# board1.net
KiCad netlist of a schematic drawn in Altium Designer
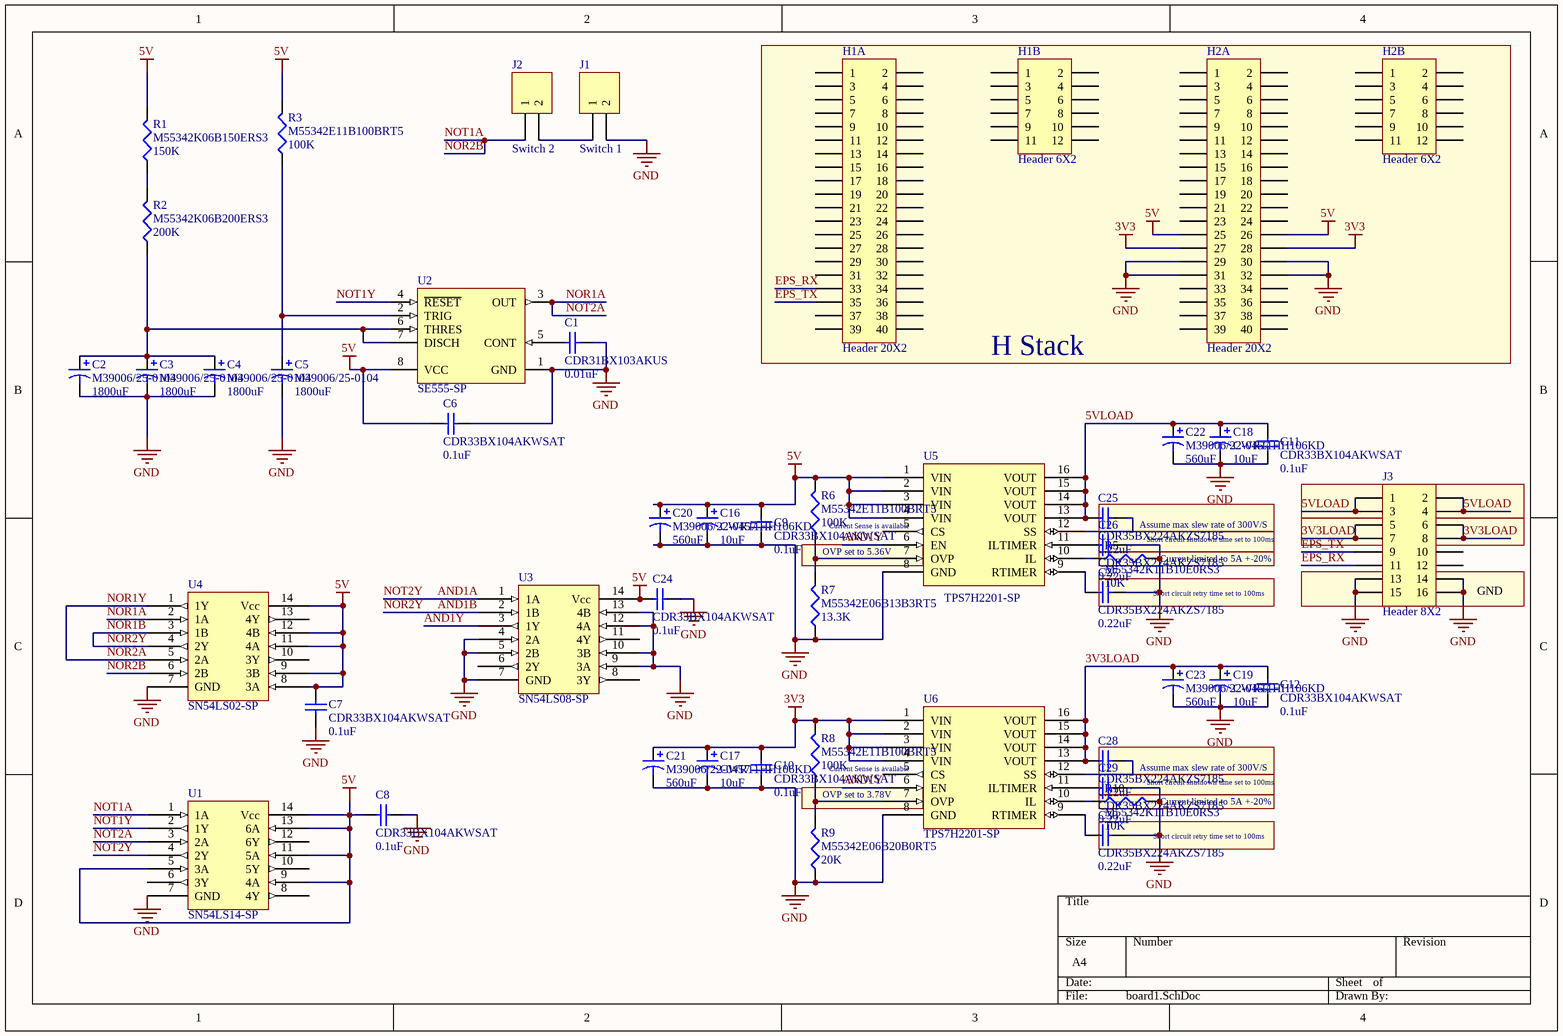
[diagram p0: board1.SchDoc]

(export (version "E")
  (design (tool "Eeschema 10.0.6"))
  (components
    (comp (ref "C1")
      (value "CDR31BX103AKUS")
      (footprint "*RESC2012X64N")
      (description "0.01uF")
      (fields (field (name "ALTIUM_VALUE") "0.01uF"))
      (libsource (lib "Capacitors") (part "CDR31BX103AKUS"))
    )
    (comp (ref "C2")
      (value "M39006/25-0104")
      (footprint "M39006/25-0104")
      (description "1800uF")
      (fields (field (name "ALTIUM_VALUE") "1800uF"))
      (libsource (lib "Capacitors") (part "M39006/25-0104"))
    )
    (comp (ref "C3")
      (value "M39006/25-0104")
      (footprint "M39006/25-0104")
      (description "1800uF")
      (fields (field (name "ALTIUM_VALUE") "1800uF"))
      (libsource (lib "Capacitors") (part "M39006/25-0104"))
    )
    (comp (ref "C4")
      (value "M39006/25-0104")
      (footprint "M39006/25-0104")
      (description "1800uF")
      (fields (field (name "ALTIUM_VALUE") "1800uF"))
      (libsource (lib "Capacitors") (part "M39006/25-0104"))
    )
    (comp (ref "C5")
      (value "M39006/25-0104")
      (footprint "M39006/25-0104")
      (description "1800uF")
      (fields (field (name "ALTIUM_VALUE") "1800uF"))
      (libsource (lib "Capacitors") (part "M39006/25-0104"))
    )
    (comp (ref "C6")
      (value "CDR33BX104AKWSAT")
      (footprint "*CAPC3225X125N")
      (description "0.1uF")
      (fields (field (name "ALTIUM_VALUE") "0.1uF"))
      (libsource (lib "Capacitors") (part "CDR33BX104AKWSAT"))
    )
    (comp (ref "C7")
      (value "CDR33BX104AKWSAT")
      (footprint "*CAPC3225X125N")
      (description "0.1uF")
      (fields (field (name "ALTIUM_VALUE") "0.1uF"))
      (libsource (lib "Capacitors") (part "CDR33BX104AKWSAT"))
    )
    (comp (ref "C8")
      (value "CDR33BX104AKWSAT")
      (footprint "*CAPC3225X125N")
      (description "0.1uF")
      (fields (field (name "ALTIUM_VALUE") "0.1uF"))
      (libsource (lib "Capacitors") (part "CDR33BX104AKWSAT"))
    )
    (comp (ref "C9")
      (value "CDR33BX104AKWSAT")
      (footprint "*CAPC3225X125N")
      (description "0.1uF")
      (fields (field (name "ALTIUM_VALUE") "0.1uF"))
      (libsource (lib "Capacitors") (part "CDR33BX104AKWSAT"))
    )
    (comp (ref "C10")
      (value "CDR33BX104AKWSAT")
      (footprint "*CAPC3225X125N")
      (description "0.1uF")
      (fields (field (name "ALTIUM_VALUE") "0.1uF"))
      (libsource (lib "Capacitors") (part "CDR33BX104AKWSAT"))
    )
    (comp (ref "C11")
      (value "CDR33BX104AKWSAT")
      (footprint "*CAPC3225X125N")
      (description "0.1uF")
      (fields (field (name "ALTIUM_VALUE") "0.1uF"))
      (libsource (lib "Capacitors") (part "CDR33BX104AKWSAT"))
    )
    (comp (ref "C12")
      (value "CDR33BX104AKWSAT")
      (footprint "*CAPC3225X125N")
      (description "0.1uF")
      (fields (field (name "ALTIUM_VALUE") "0.1uF"))
      (libsource (lib "Capacitors") (part "CDR33BX104AKWSAT"))
    )
    (comp (ref "C16")
      (value "CWR11HH106KD")
      (footprint "*CAPCP6032X280N")
      (description "10uF")
      (fields (field (name "ALTIUM_VALUE") "10uF"))
      (libsource (lib "Capacitors") (part "CWR11HH106KD"))
    )
    (comp (ref "C17")
      (value "CWR11HH106KD")
      (footprint "*CAPCP6032X280N")
      (description "10uF")
      (fields (field (name "ALTIUM_VALUE") "10uF"))
      (libsource (lib "Capacitors") (part "CWR11HH106KD"))
    )
    (comp (ref "C18")
      (value "CWR11HH106KD")
      (footprint "*CAPCP6032X280N")
      (description "10uF")
      (fields (field (name "ALTIUM_VALUE") "10uF"))
      (libsource (lib "Capacitors") (part "CWR11HH106KD"))
    )
    (comp (ref "C19")
      (value "CWR11HH106KD")
      (footprint "*CAPCP6032X280N")
      (description "10uF")
      (fields (field (name "ALTIUM_VALUE") "10uF"))
      (libsource (lib "Capacitors") (part "CWR11HH106KD"))
    )
    (comp (ref "C20")
      (value "M39006/22-0457")
      (footprint "M39006/22-0457")
      (description "560uF")
      (fields (field (name "ALTIUM_VALUE") "560uF"))
      (libsource (lib "Capacitors") (part "M39006/22-0457"))
    )
    (comp (ref "C21")
      (value "M39006/22-0457")
      (footprint "M39006/22-0457")
      (description "560uF")
      (fields (field (name "ALTIUM_VALUE") "560uF"))
      (libsource (lib "Capacitors") (part "M39006/22-0457"))
    )
    (comp (ref "C22")
      (value "M39006/22-0457")
      (footprint "M39006/22-0457")
      (description "560uF")
      (fields (field (name "ALTIUM_VALUE") "560uF"))
      (libsource (lib "Capacitors") (part "M39006/22-0457"))
    )
    (comp (ref "C23")
      (value "M39006/22-0457")
      (footprint "M39006/22-0457")
      (description "560uF")
      (fields (field (name "ALTIUM_VALUE") "560uF"))
      (libsource (lib "Capacitors") (part "M39006/22-0457"))
    )
    (comp (ref "C24")
      (value "CDR33BX104AKWSAT")
      (footprint "*CAPC3225X125N")
      (description "0.1uF")
      (fields (field (name "ALTIUM_VALUE") "0.1uF"))
      (libsource (lib "Capacitors") (part "CDR33BX104AKWSAT"))
    )
    (comp (ref "C25")
      (value "CDR35BX224AKZS7185")
      (footprint "*CAPC4663X340N")
      (description "0.22uF")
      (fields (field (name "ALTIUM_VALUE") "0.22uF"))
      (libsource (lib "Capacitors") (part "CDR35BX224AKZS7185"))
    )
    (comp (ref "C26")
      (value "CDR35BX224AKZS7185")
      (footprint "*CAPC4663X340N")
      (description "0.22uF")
      (fields (field (name "ALTIUM_VALUE") "0.22uF"))
      (libsource (lib "Capacitors") (part "CDR35BX224AKZS7185"))
    )
    (comp (ref "C27")
      (value "CDR35BX224AKZS7185")
      (footprint "*CAPC4663X340N")
      (description "0.22uF")
      (fields (field (name "ALTIUM_VALUE") "0.22uF"))
      (libsource (lib "Capacitors") (part "CDR35BX224AKZS7185"))
    )
    (comp (ref "C28")
      (value "CDR35BX224AKZS7185")
      (footprint "*CAPC4663X340N")
      (description "0.22uF")
      (fields (field (name "ALTIUM_VALUE") "0.22uF"))
      (libsource (lib "Capacitors") (part "CDR35BX224AKZS7185"))
    )
    (comp (ref "C29")
      (value "CDR35BX224AKZS7185")
      (footprint "*CAPC4663X340N")
      (description "0.22uF")
      (fields (field (name "ALTIUM_VALUE") "0.22uF"))
      (libsource (lib "Capacitors") (part "CDR35BX224AKZS7185"))
    )
    (comp (ref "C30")
      (value "CDR35BX224AKZS7185")
      (footprint "*CAPC4663X340N")
      (description "0.22uF")
      (fields (field (name "ALTIUM_VALUE") "0.22uF"))
      (libsource (lib "Capacitors") (part "CDR35BX224AKZS7185"))
    )
    (comp (ref "H1A")
      (value "Header 20X2")
      (footprint "HDR2X20")
      (description "Header, 20-Pin, Dual row")
      (fields (field (name "PUBLISHER") "Altium Limited"))
      (libsource (lib "Miscellaneous Connectors") (part "Header 20X2"))
    )
    (comp (ref "H1B")
      (value "Header 6X2")
      (footprint "HDR2X6")
      (description "Header, 6-Pin, Dual row")
      (fields (field (name "PUBLISHER") "Altium Limited"))
      (libsource (lib "Miscellaneous Connectors") (part "Header 6X2"))
    )
    (comp (ref "H2A")
      (value "Header 20X2")
      (footprint "HDR2X20")
      (description "Header, 20-Pin, Dual row")
      (fields (field (name "PUBLISHER") "Altium Limited"))
      (libsource (lib "Miscellaneous Connectors") (part "Header 20X2"))
    )
    (comp (ref "H2B")
      (value "Header 6X2")
      (footprint "HDR2X6")
      (description "Header, 6-Pin, Dual row")
      (fields (field (name "PUBLISHER") "Altium Limited"))
      (libsource (lib "Miscellaneous Connectors") (part "Header 6X2"))
    )
    (comp (ref "J1")
      (value "Switch 1")
      (footprint "HDR1X2")
      (description "Header, 2-Pin")
      (fields (field (name "PUBLISHER") "Altium Limited"))
      (libsource (lib "Miscellaneous Connectors") (part "Header 2"))
    )
    (comp (ref "J2")
      (value "Switch 2")
      (footprint "HDR1X2")
      (description "Header, 2-Pin")
      (fields (field (name "PUBLISHER") "Altium Limited"))
      (libsource (lib "Miscellaneous Connectors") (part "Header 2"))
    )
    (comp (ref "J3")
      (value "Header 8X2")
      (footprint "HDR2X8")
      (description "Header, 8-Pin, Dual row")
      (fields (field (name "PUBLISHER") "Altium Limited"))
      (libsource (lib "Miscellaneous Connectors") (part "Header 8X2"))
    )
    (comp (ref "R1")
      (value "M55342K06B150ERS3")
      (footprint "*RESC2012X64N")
      (description "150K")
      (fields (field (name "ALTIUM_VALUE") "150K"))
      (libsource (lib "Resistors") (part "M55342K06B150ERS3"))
    )
    (comp (ref "R2")
      (value "M55342K06B200ERS3")
      (footprint "*RESC2012X64N")
      (description "200K")
      (fields (field (name "ALTIUM_VALUE") "200K"))
      (libsource (lib "Resistors") (part "M55342K06B200ERS3"))
    )
    (comp (ref "R3")
      (value "M55342E11B100BRT5")
      (footprint "*RESC1005X84N")
      (description "100K")
      (fields (field (name "ALTIUM_VALUE") "100K"))
      (libsource (lib "Resistors") (part "M55342E11B100BRT5"))
    )
    (comp (ref "R5")
      (value "M55342K11B10E0RS3")
      (footprint "*RESC1005X84N")
      (description "10K")
      (fields (field (name "ALTIUM_VALUE") "10K"))
      (libsource (lib "Resistors") (part "M55342K11B10E0RS3"))
    )
    (comp (ref "R6")
      (value "M55342E11B100BRT5")
      (footprint "*RESC1005X84N")
      (description "100K")
      (fields (field (name "ALTIUM_VALUE") "100K"))
      (libsource (lib "Resistors") (part "M55342E11B100BRT5"))
    )
    (comp (ref "R7")
      (value "M55342E06B13B3RT5")
      (footprint "*RESC2012X64N")
      (description "13.3K")
      (fields (field (name "ALTIUM_VALUE") "13.3K"))
      (libsource (lib "Resistors") (part "M55342E06B13B3RT5"))
    )
    (comp (ref "R8")
      (value "M55342E11B100BRT5")
      (footprint "*RESC1005X84N")
      (description "100K")
      (fields (field (name "ALTIUM_VALUE") "100K"))
      (libsource (lib "Resistors") (part "M55342E11B100BRT5"))
    )
    (comp (ref "R9")
      (value "M55342E06B20B0RT5")
      (footprint "*RESC2012X64N")
      (description "20K")
      (fields (field (name "ALTIUM_VALUE") "20K"))
      (libsource (lib "Resistors") (part "M55342E06B20B0RT5"))
    )
    (comp (ref "R10")
      (value "M55342K11B10E0RS3")
      (footprint "*RESC1005X84N")
      (description "10K")
      (fields (field (name "ALTIUM_VALUE") "10K"))
      (libsource (lib "Resistors") (part "M55342K11B10E0RS3"))
    )
    (comp (ref "U1")
      (value "SN54LS14-SP")
      (footprint "SN54LS14-SP")
      (description "Invertor")
      (libsource (lib "SN54LS14-SP") (part "SN54LS14-SP"))
    )
    (comp (ref "U2")
      (value "SE555-SP")
      (footprint "P0008A")
      (description "Precision Timer, 4.5 to 16 V, -55 to 125 degC, 8-Pin DIP, Pb-Free, Tube")
      (fields (field (name "MANUFACTURER") "TexasInstruments"))
      (libsource (lib "Altium Content Vault") (part "TI-NE555-P8"))
    )
    (comp (ref "U3")
      (value "SN54LS08-SP")
      (footprint "SN54LS08-SP")
      (description "AND gate")
      (libsource (lib "SN54LS08-SP") (part "SN54LS08-SP"))
    )
    (comp (ref "U4")
      (value "SN54LS02-SP")
      (footprint "SN54LS02-SP")
      (description "NOR gate")
      (libsource (lib "SN54LS02-SP") (part "SN54LS02-SP"))
    )
    (comp (ref "U5")
      (value "TPS7H2201-SP")
      (footprint "TPS7H2201-SP")
      (libsource (lib "TPS7H2201-SP") (part "TPS7H2201-SP"))
    )
    (comp (ref "U6")
      (value "TPS7H2201-SP")
      (footprint "TPS7H2201-SP")
      (libsource (lib "TPS7H2201-SP") (part "TPS7H2201-SP"))
    )
  )
  (nets
    (net (code "1") (name "/3V3LOAD") (class "Default")
      (node (ref "C12") (pin "1") (pinfunction "1_1") (pintype "passive"))
      (node (ref "C19") (pin "1") (pinfunction "1_1") (pintype "passive"))
      (node (ref "C23") (pin "1") (pinfunction "1_1") (pintype "passive"))
      (node (ref "C28") (pin "1") (pinfunction "1_1") (pintype "passive"))
      (node (ref "J3") (pin "5") (pinfunction "5_5") (pintype "passive"))
      (node (ref "J3") (pin "6") (pinfunction "6_6") (pintype "passive"))
      (node (ref "J3") (pin "7") (pinfunction "7_7") (pintype "passive"))
      (node (ref "J3") (pin "8") (pinfunction "8_8") (pintype "passive"))
      (node (ref "U6") (pin "13") (pinfunction "VOUT_13") (pintype "power_in"))
      (node (ref "U6") (pin "14") (pinfunction "VOUT_14") (pintype "power_in"))
      (node (ref "U6") (pin "15") (pinfunction "VOUT_15") (pintype "power_in"))
      (node (ref "U6") (pin "16") (pinfunction "VOUT_16") (pintype "power_in"))
    )
    (net (code "2") (name "/5VLOAD") (class "Default")
      (node (ref "C11") (pin "1") (pinfunction "1_1") (pintype "passive"))
      (node (ref "C18") (pin "1") (pinfunction "1_1") (pintype "passive"))
      (node (ref "C22") (pin "1") (pinfunction "1_1") (pintype "passive"))
      (node (ref "C25") (pin "1") (pinfunction "1_1") (pintype "passive"))
      (node (ref "J3") (pin "1") (pinfunction "1_1") (pintype "passive"))
      (node (ref "J3") (pin "2") (pinfunction "2_2") (pintype "passive"))
      (node (ref "J3") (pin "3") (pinfunction "3_3") (pintype "passive"))
      (node (ref "J3") (pin "4") (pinfunction "4_4") (pintype "passive"))
      (node (ref "U5") (pin "13") (pinfunction "VOUT_13") (pintype "power_in"))
      (node (ref "U5") (pin "14") (pinfunction "VOUT_14") (pintype "power_in"))
      (node (ref "U5") (pin "15") (pinfunction "VOUT_15") (pintype "power_in"))
      (node (ref "U5") (pin "16") (pinfunction "VOUT_16") (pintype "power_in"))
    )
    (net (code "3") (name "/AND1A") (class "Default")
      (node (ref "U1") (pin "4") (pinfunction "2Y_4") (pintype "output"))
      (node (ref "U3") (pin "1") (pinfunction "1A_1") (pintype "input"))
    )
    (net (code "4") (name "/AND1B") (class "Default")
      (node (ref "U3") (pin "2") (pinfunction "1B_2") (pintype "input"))
      (node (ref "U4") (pin "3") (pinfunction "1B_3") (pintype "input"))
      (node (ref "U4") (pin "4") (pinfunction "2Y_4") (pintype "output"))
    )
    (net (code "5") (name "/AND1Y") (class "Default")
      (node (ref "U3") (pin "3") (pinfunction "1Y_3") (pintype "output"))
      (node (ref "U5") (pin "6") (pinfunction "EN_6") (pintype "input"))
      (node (ref "U6") (pin "6") (pinfunction "EN_6") (pintype "input"))
    )
    (net (code "6") (name "/EPS_RX") (class "Default")
      (node (ref "H1A") (pin "33") (pinfunction "33_33") (pintype "passive"))
      (node (ref "J3") (pin "11") (pinfunction "11_11") (pintype "passive"))
    )
    (net (code "7") (name "/EPS_TX") (class "Default")
      (node (ref "H1A") (pin "35") (pinfunction "35_35") (pintype "passive"))
      (node (ref "J3") (pin "9") (pinfunction "9_9") (pintype "passive"))
    )
    (net (code "8") (name "/NOR1A") (class "Default")
      (node (ref "U1") (pin "3") (pinfunction "2A_3") (pintype "input"))
      (node (ref "U2") (pin "3") (pinfunction "OUT_3") (pintype "output"))
      (node (ref "U4") (pin "2") (pinfunction "1A_2") (pintype "input"))
    )
    (net (code "9") (name "/NOR1Y") (class "Default")
      (node (ref "U4") (pin "1") (pinfunction "1Y_1") (pintype "output"))
      (node (ref "U4") (pin "5") (pinfunction "2A_5") (pintype "input"))
    )
    (net (code "10") (name "/NOR2B") (class "Default")
      (node (ref "J2") (pin "1") (pinfunction "1_1") (pintype "passive"))
      (node (ref "U1") (pin "1") (pinfunction "1A_1") (pintype "input"))
      (node (ref "U4") (pin "6") (pinfunction "2B_6") (pintype "input"))
    )
    (net (code "11") (name "/NOT1Y") (class "Default")
      (node (ref "U1") (pin "2") (pinfunction "1Y_2") (pintype "output"))
      (node (ref "U2") (pin "4") (pinfunction "~{RESET}_4") (pintype "input"))
    )
    (net (code "12") (name "3V3") (class "Default")
      (node (ref "C10") (pin "1") (pinfunction "1_1") (pintype "passive"))
      (node (ref "C17") (pin "1") (pinfunction "1_1") (pintype "passive"))
      (node (ref "C21") (pin "1") (pinfunction "1_1") (pintype "passive"))
      (node (ref "H2A") (pin "27") (pinfunction "27_27") (pintype "passive"))
      (node (ref "H2A") (pin "28") (pinfunction "28_28") (pintype "passive"))
      (node (ref "R8") (pin "2") (pinfunction "2_2") (pintype "passive"))
      (node (ref "U6") (pin "1") (pinfunction "VIN_1") (pintype "power_in"))
      (node (ref "U6") (pin "2") (pinfunction "VIN_2") (pintype "power_in"))
      (node (ref "U6") (pin "3") (pinfunction "VIN_3") (pintype "power_in"))
      (node (ref "U6") (pin "4") (pinfunction "VIN_4") (pintype "power_in"))
    )
    (net (code "13") (name "5V") (class "Default")
      (node (ref "C16") (pin "1") (pinfunction "1_1") (pintype "passive"))
      (node (ref "C20") (pin "1") (pinfunction "1_1") (pintype "passive"))
      (node (ref "C24") (pin "1") (pinfunction "1_1") (pintype "passive"))
      (node (ref "C6") (pin "1") (pinfunction "1_1") (pintype "passive"))
      (node (ref "C7") (pin "2") (pinfunction "2_2") (pintype "passive"))
      (node (ref "C8") (pin "2") (pinfunction "2_2") (pintype "passive"))
      (node (ref "C9") (pin "1") (pinfunction "1_1") (pintype "passive"))
      (node (ref "H2A") (pin "25") (pinfunction "25_25") (pintype "passive"))
      (node (ref "H2A") (pin "26") (pinfunction "26_26") (pintype "passive"))
      (node (ref "R1") (pin "2") (pinfunction "2_2") (pintype "passive"))
      (node (ref "R3") (pin "2") (pinfunction "2_2") (pintype "passive"))
      (node (ref "R6") (pin "2") (pinfunction "2_2") (pintype "passive"))
      (node (ref "U1") (pin "11") (pinfunction "5A_11") (pintype "input"))
      (node (ref "U1") (pin "13") (pinfunction "6A_13") (pintype "input"))
      (node (ref "U1") (pin "14") (pinfunction "Vcc_14") (pintype "power_in"))
      (node (ref "U1") (pin "5") (pinfunction "3A_5") (pintype "input"))
      (node (ref "U1") (pin "9") (pinfunction "4A_9") (pintype "input"))
      (node (ref "U2") (pin "8") (pinfunction "VCC_8") (pintype "power_in"))
      (node (ref "U3") (pin "14") (pinfunction "Vcc_14") (pintype "power_in"))
      (node (ref "U4") (pin "11") (pinfunction "4A_11") (pintype "input"))
      (node (ref "U4") (pin "12") (pinfunction "4B_12") (pintype "input"))
      (node (ref "U4") (pin "14") (pinfunction "Vcc_14") (pintype "power_in"))
      (node (ref "U4") (pin "8") (pinfunction "3A_8") (pintype "input"))
      (node (ref "U4") (pin "9") (pinfunction "3B_9") (pintype "input"))
      (node (ref "U5") (pin "1") (pinfunction "VIN_1") (pintype "power_in"))
      (node (ref "U5") (pin "2") (pinfunction "VIN_2") (pintype "power_in"))
      (node (ref "U5") (pin "3") (pinfunction "VIN_3") (pintype "power_in"))
      (node (ref "U5") (pin "4") (pinfunction "VIN_4") (pintype "power_in"))
    )
    (net (code "14") (name "GND") (class "Default")
      (node (ref "C1") (pin "2") (pinfunction "2_2") (pintype "passive"))
      (node (ref "C10") (pin "2") (pinfunction "2_2") (pintype "passive"))
      (node (ref "C11") (pin "2") (pinfunction "2_2") (pintype "passive"))
      (node (ref "C12") (pin "2") (pinfunction "2_2") (pintype "passive"))
      (node (ref "C16") (pin "2") (pinfunction "2_2") (pintype "passive"))
      (node (ref "C17") (pin "2") (pinfunction "2_2") (pintype "passive"))
      (node (ref "C18") (pin "2") (pinfunction "2_2") (pintype "passive"))
      (node (ref "C19") (pin "2") (pinfunction "2_2") (pintype "passive"))
      (node (ref "C2") (pin "2") (pinfunction "2_2") (pintype "passive"))
      (node (ref "C20") (pin "2") (pinfunction "2_2") (pintype "passive"))
      (node (ref "C21") (pin "2") (pinfunction "2_2") (pintype "passive"))
      (node (ref "C22") (pin "2") (pinfunction "2_2") (pintype "passive"))
      (node (ref "C23") (pin "2") (pinfunction "2_2") (pintype "passive"))
      (node (ref "C24") (pin "2") (pinfunction "2_2") (pintype "passive"))
      (node (ref "C26") (pin "2") (pinfunction "2_2") (pintype "passive"))
      (node (ref "C27") (pin "2") (pinfunction "2_2") (pintype "passive"))
      (node (ref "C29") (pin "2") (pinfunction "2_2") (pintype "passive"))
      (node (ref "C3") (pin "2") (pinfunction "2_2") (pintype "passive"))
      (node (ref "C30") (pin "2") (pinfunction "2_2") (pintype "passive"))
      (node (ref "C4") (pin "2") (pinfunction "2_2") (pintype "passive"))
      (node (ref "C5") (pin "2") (pinfunction "2_2") (pintype "passive"))
      (node (ref "C6") (pin "2") (pinfunction "2_2") (pintype "passive"))
      (node (ref "C7") (pin "1") (pinfunction "1_1") (pintype "passive"))
      (node (ref "C8") (pin "1") (pinfunction "1_1") (pintype "passive"))
      (node (ref "C9") (pin "2") (pinfunction "2_2") (pintype "passive"))
      (node (ref "H2A") (pin "29") (pinfunction "29_29") (pintype "passive"))
      (node (ref "H2A") (pin "30") (pinfunction "30_30") (pintype "passive"))
      (node (ref "H2A") (pin "31") (pinfunction "31_31") (pintype "passive"))
      (node (ref "H2A") (pin "32") (pinfunction "32_32") (pintype "passive"))
      (node (ref "J1") (pin "2") (pinfunction "2_2") (pintype "passive"))
      (node (ref "J3") (pin "13") (pinfunction "13_13") (pintype "passive"))
      (node (ref "J3") (pin "14") (pinfunction "14_14") (pintype "passive"))
      (node (ref "J3") (pin "15") (pinfunction "15_15") (pintype "passive"))
      (node (ref "J3") (pin "16") (pinfunction "16_16") (pintype "passive"))
      (node (ref "R10") (pin "2") (pinfunction "2_2") (pintype "passive"))
      (node (ref "R5") (pin "2") (pinfunction "2_2") (pintype "passive"))
      (node (ref "R7") (pin "1") (pinfunction "1_1") (pintype "passive"))
      (node (ref "R9") (pin "1") (pinfunction "1_1") (pintype "passive"))
      (node (ref "U1") (pin "7") (pinfunction "GND_7") (pintype "power_in"))
      (node (ref "U2") (pin "1") (pinfunction "GND_1") (pintype "power_in"))
      (node (ref "U3") (pin "10") (pinfunction "3B_10") (pintype "input"))
      (node (ref "U3") (pin "12") (pinfunction "4A_12") (pintype "input"))
      (node (ref "U3") (pin "13") (pinfunction "4B_13") (pintype "input"))
      (node (ref "U3") (pin "4") (pinfunction "2A_4") (pintype "input"))
      (node (ref "U3") (pin "5") (pinfunction "2B_5") (pintype "input"))
      (node (ref "U3") (pin "7") (pinfunction "GND_7") (pintype "power_in"))
      (node (ref "U3") (pin "9") (pinfunction "3A_9") (pintype "input"))
      (node (ref "U4") (pin "7") (pinfunction "GND_7") (pintype "power_in"))
      (node (ref "U5") (pin "8") (pinfunction "GND_8") (pintype "power_in"))
      (node (ref "U6") (pin "8") (pinfunction "GND_8") (pintype "power_in"))
    )
    (net (code "15") (name "Net-(J1-Pad1)") (class "Default")
      (node (ref "J1") (pin "1") (pinfunction "1_1") (pintype "passive"))
      (node (ref "J2") (pin "2") (pinfunction "2_2") (pintype "passive"))
    )
    (net (code "16") (name "Net-(R1-Pad1)") (class "Default")
      (node (ref "R1") (pin "1") (pinfunction "1_1") (pintype "passive"))
      (node (ref "R2") (pin "2") (pinfunction "2_2") (pintype "passive"))
    )
    (net (code "17") (name "Net-(U2-CONT)") (class "Default")
      (node (ref "C1") (pin "1") (pinfunction "1_1") (pintype "passive"))
      (node (ref "U2") (pin "5") (pinfunction "CONT_5") (pintype "input"))
    )
    (net (code "18") (name "Net-(U2-DISCH)") (class "Default")
      (node (ref "C2") (pin "1") (pinfunction "1_1") (pintype "passive"))
      (node (ref "C3") (pin "1") (pinfunction "1_1") (pintype "passive"))
      (node (ref "C4") (pin "1") (pinfunction "1_1") (pintype "passive"))
      (node (ref "R2") (pin "1") (pinfunction "1_1") (pintype "passive"))
      (node (ref "U2") (pin "6") (pinfunction "THRES_6") (pintype "input"))
      (node (ref "U2") (pin "7") (pinfunction "DISCH_7") (pintype "open_collector"))
    )
    (net (code "19") (name "Net-(U2-TRIG)") (class "Default")
      (node (ref "C5") (pin "1") (pinfunction "1_1") (pintype "passive"))
      (node (ref "R3") (pin "1") (pinfunction "1_1") (pintype "passive"))
      (node (ref "U2") (pin "2") (pinfunction "TRIG_2") (pintype "input"))
    )
    (net (code "20") (name "Net-(U5-IL)") (class "Default")
      (node (ref "R5") (pin "1") (pinfunction "1_1") (pintype "passive"))
      (node (ref "U5") (pin "10") (pinfunction "IL_10") (pintype "bidirectional"))
    )
    (net (code "21") (name "Net-(U5-ILTIMER)") (class "Default")
      (node (ref "C26") (pin "1") (pinfunction "1_1") (pintype "passive"))
      (node (ref "U5") (pin "11") (pinfunction "ILTIMER_11") (pintype "input"))
    )
    (net (code "22") (name "Net-(U5-OVP)") (class "Default")
      (node (ref "R6") (pin "1") (pinfunction "1_1") (pintype "passive"))
      (node (ref "R7") (pin "2") (pinfunction "2_2") (pintype "passive"))
      (node (ref "U5") (pin "7") (pinfunction "OVP_7") (pintype "input"))
    )
    (net (code "23") (name "Net-(U5-RTIMER)") (class "Default")
      (node (ref "C27") (pin "1") (pinfunction "1_1") (pintype "passive"))
      (node (ref "U5") (pin "9") (pinfunction "RTIMER_9") (pintype "bidirectional"))
    )
    (net (code "24") (name "Net-(U5-SS)") (class "Default")
      (node (ref "C25") (pin "2") (pinfunction "2_2") (pintype "passive"))
      (node (ref "U5") (pin "12") (pinfunction "SS_12") (pintype "bidirectional"))
    )
    (net (code "25") (name "Net-(U6-IL)") (class "Default")
      (node (ref "R10") (pin "1") (pinfunction "1_1") (pintype "passive"))
      (node (ref "U6") (pin "10") (pinfunction "IL_10") (pintype "bidirectional"))
    )
    (net (code "26") (name "Net-(U6-ILTIMER)") (class "Default")
      (node (ref "C29") (pin "1") (pinfunction "1_1") (pintype "passive"))
      (node (ref "U6") (pin "11") (pinfunction "ILTIMER_11") (pintype "input"))
    )
    (net (code "27") (name "Net-(U6-OVP)") (class "Default")
      (node (ref "R8") (pin "1") (pinfunction "1_1") (pintype "passive"))
      (node (ref "R9") (pin "2") (pinfunction "2_2") (pintype "passive"))
      (node (ref "U6") (pin "7") (pinfunction "OVP_7") (pintype "input"))
    )
    (net (code "28") (name "Net-(U6-RTIMER)") (class "Default")
      (node (ref "C30") (pin "1") (pinfunction "1_1") (pintype "passive"))
      (node (ref "U6") (pin "9") (pinfunction "RTIMER_9") (pintype "bidirectional"))
    )
    (net (code "29") (name "Net-(U6-SS)") (class "Default")
      (node (ref "C28") (pin "2") (pinfunction "2_2") (pintype "passive"))
      (node (ref "U6") (pin "12") (pinfunction "SS_12") (pintype "bidirectional"))
    )
    (net (code "30") (name "unconnected-(H1A-Pad1)") (class "Default")
      (node (ref "H1A") (pin "1") (pinfunction "1_1") (pintype "passive"))
    )
    (net (code "31") (name "unconnected-(H1A-Pad2)") (class "Default")
      (node (ref "H1A") (pin "2") (pinfunction "2_2") (pintype "passive"))
    )
    (net (code "32") (name "unconnected-(H1A-Pad3)") (class "Default")
      (node (ref "H1A") (pin "3") (pinfunction "3_3") (pintype "passive"))
    )
    (net (code "33") (name "unconnected-(H1A-Pad4)") (class "Default")
      (node (ref "H1A") (pin "4") (pinfunction "4_4") (pintype "passive"))
    )
    (net (code "34") (name "unconnected-(H1A-Pad5)") (class "Default")
      (node (ref "H1A") (pin "5") (pinfunction "5_5") (pintype "passive"))
    )
    (net (code "35") (name "unconnected-(H1A-Pad6)") (class "Default")
      (node (ref "H1A") (pin "6") (pinfunction "6_6") (pintype "passive"))
    )
    (net (code "36") (name "unconnected-(H1A-Pad7)") (class "Default")
      (node (ref "H1A") (pin "7") (pinfunction "7_7") (pintype "passive"))
    )
    (net (code "37") (name "unconnected-(H1A-Pad8)") (class "Default")
      (node (ref "H1A") (pin "8") (pinfunction "8_8") (pintype "passive"))
    )
    (net (code "38") (name "unconnected-(H1A-Pad9)") (class "Default")
      (node (ref "H1A") (pin "9") (pinfunction "9_9") (pintype "passive"))
    )
    (net (code "39") (name "unconnected-(H1A-Pad10)") (class "Default")
      (node (ref "H1A") (pin "10") (pinfunction "10_10") (pintype "passive"))
    )
    (net (code "40") (name "unconnected-(H1A-Pad11)") (class "Default")
      (node (ref "H1A") (pin "11") (pinfunction "11_11") (pintype "passive"))
    )
    (net (code "41") (name "unconnected-(H1A-Pad12)") (class "Default")
      (node (ref "H1A") (pin "12") (pinfunction "12_12") (pintype "passive"))
    )
    (net (code "42") (name "unconnected-(H1A-Pad13)") (class "Default")
      (node (ref "H1A") (pin "13") (pinfunction "13_13") (pintype "passive"))
    )
    (net (code "43") (name "unconnected-(H1A-Pad14)") (class "Default")
      (node (ref "H1A") (pin "14") (pinfunction "14_14") (pintype "passive"))
    )
    (net (code "44") (name "unconnected-(H1A-Pad15)") (class "Default")
      (node (ref "H1A") (pin "15") (pinfunction "15_15") (pintype "passive"))
    )
    (net (code "45") (name "unconnected-(H1A-Pad16)") (class "Default")
      (node (ref "H1A") (pin "16") (pinfunction "16_16") (pintype "passive"))
    )
    (net (code "46") (name "unconnected-(H1A-Pad17)") (class "Default")
      (node (ref "H1A") (pin "17") (pinfunction "17_17") (pintype "passive"))
    )
    (net (code "47") (name "unconnected-(H1A-Pad18)") (class "Default")
      (node (ref "H1A") (pin "18") (pinfunction "18_18") (pintype "passive"))
    )
    (net (code "48") (name "unconnected-(H1A-Pad19)") (class "Default")
      (node (ref "H1A") (pin "19") (pinfunction "19_19") (pintype "passive"))
    )
    (net (code "49") (name "unconnected-(H1A-Pad20)") (class "Default")
      (node (ref "H1A") (pin "20") (pinfunction "20_20") (pintype "passive"))
    )
    (net (code "50") (name "unconnected-(H1A-Pad21)") (class "Default")
      (node (ref "H1A") (pin "21") (pinfunction "21_21") (pintype "passive"))
    )
    (net (code "51") (name "unconnected-(H1A-Pad22)") (class "Default")
      (node (ref "H1A") (pin "22") (pinfunction "22_22") (pintype "passive"))
    )
    (net (code "52") (name "unconnected-(H1A-Pad23)") (class "Default")
      (node (ref "H1A") (pin "23") (pinfunction "23_23") (pintype "passive"))
    )
    (net (code "53") (name "unconnected-(H1A-Pad24)") (class "Default")
      (node (ref "H1A") (pin "24") (pinfunction "24_24") (pintype "passive"))
    )
    (net (code "54") (name "unconnected-(H1A-Pad25)") (class "Default")
      (node (ref "H1A") (pin "25") (pinfunction "25_25") (pintype "passive"))
    )
    (net (code "55") (name "unconnected-(H1A-Pad26)") (class "Default")
      (node (ref "H1A") (pin "26") (pinfunction "26_26") (pintype "passive"))
    )
    (net (code "56") (name "unconnected-(H1A-Pad27)") (class "Default")
      (node (ref "H1A") (pin "27") (pinfunction "27_27") (pintype "passive"))
    )
    (net (code "57") (name "unconnected-(H1A-Pad28)") (class "Default")
      (node (ref "H1A") (pin "28") (pinfunction "28_28") (pintype "passive"))
    )
    (net (code "58") (name "unconnected-(H1A-Pad29)") (class "Default")
      (node (ref "H1A") (pin "29") (pinfunction "29_29") (pintype "passive"))
    )
    (net (code "59") (name "unconnected-(H1A-Pad30)") (class "Default")
      (node (ref "H1A") (pin "30") (pinfunction "30_30") (pintype "passive"))
    )
    (net (code "60") (name "unconnected-(H1A-Pad31)") (class "Default")
      (node (ref "H1A") (pin "31") (pinfunction "31_31") (pintype "passive"))
    )
    (net (code "61") (name "unconnected-(H1A-Pad32)") (class "Default")
      (node (ref "H1A") (pin "32") (pinfunction "32_32") (pintype "passive"))
    )
    (net (code "62") (name "unconnected-(H1A-Pad34)") (class "Default")
      (node (ref "H1A") (pin "34") (pinfunction "34_34") (pintype "passive"))
    )
    (net (code "63") (name "unconnected-(H1A-Pad36)") (class "Default")
      (node (ref "H1A") (pin "36") (pinfunction "36_36") (pintype "passive"))
    )
    (net (code "64") (name "unconnected-(H1A-Pad37)") (class "Default")
      (node (ref "H1A") (pin "37") (pinfunction "37_37") (pintype "passive"))
    )
    (net (code "65") (name "unconnected-(H1A-Pad38)") (class "Default")
      (node (ref "H1A") (pin "38") (pinfunction "38_38") (pintype "passive"))
    )
    (net (code "66") (name "unconnected-(H1A-Pad39)") (class "Default")
      (node (ref "H1A") (pin "39") (pinfunction "39_39") (pintype "passive"))
    )
    (net (code "67") (name "unconnected-(H1A-Pad40)") (class "Default")
      (node (ref "H1A") (pin "40") (pinfunction "40_40") (pintype "passive"))
    )
    (net (code "68") (name "unconnected-(H1B-Pad1)") (class "Default")
      (node (ref "H1B") (pin "1") (pinfunction "1_1") (pintype "passive"))
    )
    (net (code "69") (name "unconnected-(H1B-Pad2)") (class "Default")
      (node (ref "H1B") (pin "2") (pinfunction "2_2") (pintype "passive"))
    )
    (net (code "70") (name "unconnected-(H1B-Pad3)") (class "Default")
      (node (ref "H1B") (pin "3") (pinfunction "3_3") (pintype "passive"))
    )
    (net (code "71") (name "unconnected-(H1B-Pad4)") (class "Default")
      (node (ref "H1B") (pin "4") (pinfunction "4_4") (pintype "passive"))
    )
    (net (code "72") (name "unconnected-(H1B-Pad5)") (class "Default")
      (node (ref "H1B") (pin "5") (pinfunction "5_5") (pintype "passive"))
    )
    (net (code "73") (name "unconnected-(H1B-Pad6)") (class "Default")
      (node (ref "H1B") (pin "6") (pinfunction "6_6") (pintype "passive"))
    )
    (net (code "74") (name "unconnected-(H1B-Pad7)") (class "Default")
      (node (ref "H1B") (pin "7") (pinfunction "7_7") (pintype "passive"))
    )
    (net (code "75") (name "unconnected-(H1B-Pad8)") (class "Default")
      (node (ref "H1B") (pin "8") (pinfunction "8_8") (pintype "passive"))
    )
    (net (code "76") (name "unconnected-(H1B-Pad9)") (class "Default")
      (node (ref "H1B") (pin "9") (pinfunction "9_9") (pintype "passive"))
    )
    (net (code "77") (name "unconnected-(H1B-Pad10)") (class "Default")
      (node (ref "H1B") (pin "10") (pinfunction "10_10") (pintype "passive"))
    )
    (net (code "78") (name "unconnected-(H1B-Pad11)") (class "Default")
      (node (ref "H1B") (pin "11") (pinfunction "11_11") (pintype "passive"))
    )
    (net (code "79") (name "unconnected-(H1B-Pad12)") (class "Default")
      (node (ref "H1B") (pin "12") (pinfunction "12_12") (pintype "passive"))
    )
    (net (code "80") (name "unconnected-(H2A-Pad1)") (class "Default")
      (node (ref "H2A") (pin "1") (pinfunction "1_1") (pintype "passive"))
    )
    (net (code "81") (name "unconnected-(H2A-Pad2)") (class "Default")
      (node (ref "H2A") (pin "2") (pinfunction "2_2") (pintype "passive"))
    )
    (net (code "82") (name "unconnected-(H2A-Pad3)") (class "Default")
      (node (ref "H2A") (pin "3") (pinfunction "3_3") (pintype "passive"))
    )
    (net (code "83") (name "unconnected-(H2A-Pad4)") (class "Default")
      (node (ref "H2A") (pin "4") (pinfunction "4_4") (pintype "passive"))
    )
    (net (code "84") (name "unconnected-(H2A-Pad5)") (class "Default")
      (node (ref "H2A") (pin "5") (pinfunction "5_5") (pintype "passive"))
    )
    (net (code "85") (name "unconnected-(H2A-Pad6)") (class "Default")
      (node (ref "H2A") (pin "6") (pinfunction "6_6") (pintype "passive"))
    )
    (net (code "86") (name "unconnected-(H2A-Pad7)") (class "Default")
      (node (ref "H2A") (pin "7") (pinfunction "7_7") (pintype "passive"))
    )
    (net (code "87") (name "unconnected-(H2A-Pad8)") (class "Default")
      (node (ref "H2A") (pin "8") (pinfunction "8_8") (pintype "passive"))
    )
    (net (code "88") (name "unconnected-(H2A-Pad9)") (class "Default")
      (node (ref "H2A") (pin "9") (pinfunction "9_9") (pintype "passive"))
    )
    (net (code "89") (name "unconnected-(H2A-Pad10)") (class "Default")
      (node (ref "H2A") (pin "10") (pinfunction "10_10") (pintype "passive"))
    )
    (net (code "90") (name "unconnected-(H2A-Pad11)") (class "Default")
      (node (ref "H2A") (pin "11") (pinfunction "11_11") (pintype "passive"))
    )
    (net (code "91") (name "unconnected-(H2A-Pad12)") (class "Default")
      (node (ref "H2A") (pin "12") (pinfunction "12_12") (pintype "passive"))
    )
    (net (code "92") (name "unconnected-(H2A-Pad13)") (class "Default")
      (node (ref "H2A") (pin "13") (pinfunction "13_13") (pintype "passive"))
    )
    (net (code "93") (name "unconnected-(H2A-Pad14)") (class "Default")
      (node (ref "H2A") (pin "14") (pinfunction "14_14") (pintype "passive"))
    )
    (net (code "94") (name "unconnected-(H2A-Pad15)") (class "Default")
      (node (ref "H2A") (pin "15") (pinfunction "15_15") (pintype "passive"))
    )
    (net (code "95") (name "unconnected-(H2A-Pad16)") (class "Default")
      (node (ref "H2A") (pin "16") (pinfunction "16_16") (pintype "passive"))
    )
    (net (code "96") (name "unconnected-(H2A-Pad17)") (class "Default")
      (node (ref "H2A") (pin "17") (pinfunction "17_17") (pintype "passive"))
    )
    (net (code "97") (name "unconnected-(H2A-Pad18)") (class "Default")
      (node (ref "H2A") (pin "18") (pinfunction "18_18") (pintype "passive"))
    )
    (net (code "98") (name "unconnected-(H2A-Pad19)") (class "Default")
      (node (ref "H2A") (pin "19") (pinfunction "19_19") (pintype "passive"))
    )
    (net (code "99") (name "unconnected-(H2A-Pad20)") (class "Default")
      (node (ref "H2A") (pin "20") (pinfunction "20_20") (pintype "passive"))
    )
    (net (code "100") (name "unconnected-(H2A-Pad21)") (class "Default")
      (node (ref "H2A") (pin "21") (pinfunction "21_21") (pintype "passive"))
    )
    (net (code "101") (name "unconnected-(H2A-Pad22)") (class "Default")
      (node (ref "H2A") (pin "22") (pinfunction "22_22") (pintype "passive"))
    )
    (net (code "102") (name "unconnected-(H2A-Pad23)") (class "Default")
      (node (ref "H2A") (pin "23") (pinfunction "23_23") (pintype "passive"))
    )
    (net (code "103") (name "unconnected-(H2A-Pad24)") (class "Default")
      (node (ref "H2A") (pin "24") (pinfunction "24_24") (pintype "passive"))
    )
    (net (code "104") (name "unconnected-(H2A-Pad33)") (class "Default")
      (node (ref "H2A") (pin "33") (pinfunction "33_33") (pintype "passive"))
    )
    (net (code "105") (name "unconnected-(H2A-Pad34)") (class "Default")
      (node (ref "H2A") (pin "34") (pinfunction "34_34") (pintype "passive"))
    )
    (net (code "106") (name "unconnected-(H2A-Pad35)") (class "Default")
      (node (ref "H2A") (pin "35") (pinfunction "35_35") (pintype "passive"))
    )
    (net (code "107") (name "unconnected-(H2A-Pad36)") (class "Default")
      (node (ref "H2A") (pin "36") (pinfunction "36_36") (pintype "passive"))
    )
    (net (code "108") (name "unconnected-(H2A-Pad37)") (class "Default")
      (node (ref "H2A") (pin "37") (pinfunction "37_37") (pintype "passive"))
    )
    (net (code "109") (name "unconnected-(H2A-Pad38)") (class "Default")
      (node (ref "H2A") (pin "38") (pinfunction "38_38") (pintype "passive"))
    )
    (net (code "110") (name "unconnected-(H2A-Pad39)") (class "Default")
      (node (ref "H2A") (pin "39") (pinfunction "39_39") (pintype "passive"))
    )
    (net (code "111") (name "unconnected-(H2A-Pad40)") (class "Default")
      (node (ref "H2A") (pin "40") (pinfunction "40_40") (pintype "passive"))
    )
    (net (code "112") (name "unconnected-(H2B-Pad1)") (class "Default")
      (node (ref "H2B") (pin "1") (pinfunction "1_1") (pintype "passive"))
    )
    (net (code "113") (name "unconnected-(H2B-Pad2)") (class "Default")
      (node (ref "H2B") (pin "2") (pinfunction "2_2") (pintype "passive"))
    )
    (net (code "114") (name "unconnected-(H2B-Pad3)") (class "Default")
      (node (ref "H2B") (pin "3") (pinfunction "3_3") (pintype "passive"))
    )
    (net (code "115") (name "unconnected-(H2B-Pad4)") (class "Default")
      (node (ref "H2B") (pin "4") (pinfunction "4_4") (pintype "passive"))
    )
    (net (code "116") (name "unconnected-(H2B-Pad5)") (class "Default")
      (node (ref "H2B") (pin "5") (pinfunction "5_5") (pintype "passive"))
    )
    (net (code "117") (name "unconnected-(H2B-Pad6)") (class "Default")
      (node (ref "H2B") (pin "6") (pinfunction "6_6") (pintype "passive"))
    )
    (net (code "118") (name "unconnected-(H2B-Pad7)") (class "Default")
      (node (ref "H2B") (pin "7") (pinfunction "7_7") (pintype "passive"))
    )
    (net (code "119") (name "unconnected-(H2B-Pad8)") (class "Default")
      (node (ref "H2B") (pin "8") (pinfunction "8_8") (pintype "passive"))
    )
    (net (code "120") (name "unconnected-(H2B-Pad9)") (class "Default")
      (node (ref "H2B") (pin "9") (pinfunction "9_9") (pintype "passive"))
    )
    (net (code "121") (name "unconnected-(H2B-Pad10)") (class "Default")
      (node (ref "H2B") (pin "10") (pinfunction "10_10") (pintype "passive"))
    )
    (net (code "122") (name "unconnected-(H2B-Pad11)") (class "Default")
      (node (ref "H2B") (pin "11") (pinfunction "11_11") (pintype "passive"))
    )
    (net (code "123") (name "unconnected-(H2B-Pad12)") (class "Default")
      (node (ref "H2B") (pin "12") (pinfunction "12_12") (pintype "passive"))
    )
    (net (code "124") (name "unconnected-(J3-Pad10)") (class "Default")
      (node (ref "J3") (pin "10") (pinfunction "10_10") (pintype "passive"))
    )
    (net (code "125") (name "unconnected-(J3-Pad12)") (class "Default")
      (node (ref "J3") (pin "12") (pinfunction "12_12") (pintype "passive"))
    )
    (net (code "126") (name "unconnected-(U1-3Y-Pad6)") (class "Default")
      (node (ref "U1") (pin "6") (pinfunction "3Y_6") (pintype "output"))
    )
    (net (code "127") (name "unconnected-(U1-4Y-Pad8)") (class "Default")
      (node (ref "U1") (pin "8") (pinfunction "4Y_8") (pintype "output"))
    )
    (net (code "128") (name "unconnected-(U1-5Y-Pad10)") (class "Default")
      (node (ref "U1") (pin "10") (pinfunction "5Y_10") (pintype "output"))
    )
    (net (code "129") (name "unconnected-(U1-6Y-Pad12)") (class "Default")
      (node (ref "U1") (pin "12") (pinfunction "6Y_12") (pintype "output"))
    )
    (net (code "130") (name "unconnected-(U3-2Y-Pad6)") (class "Default")
      (node (ref "U3") (pin "6") (pinfunction "2Y_6") (pintype "output"))
    )
    (net (code "131") (name "unconnected-(U3-3Y-Pad8)") (class "Default")
      (node (ref "U3") (pin "8") (pinfunction "3Y_8") (pintype "output"))
    )
    (net (code "132") (name "unconnected-(U3-4Y-Pad11)") (class "Default")
      (node (ref "U3") (pin "11") (pinfunction "4Y_11") (pintype "output"))
    )
    (net (code "133") (name "unconnected-(U4-3Y-Pad10)") (class "Default")
      (node (ref "U4") (pin "10") (pinfunction "3Y_10") (pintype "output"))
    )
    (net (code "134") (name "unconnected-(U4-4Y-Pad13)") (class "Default")
      (node (ref "U4") (pin "13") (pinfunction "4Y_13") (pintype "output"))
    )
    (net (code "135") (name "unconnected-(U5-CS-Pad5)") (class "Default")
      (node (ref "U5") (pin "5") (pinfunction "CS_5") (pintype "output"))
    )
    (net (code "136") (name "unconnected-(U6-CS-Pad5)") (class "Default")
      (node (ref "U6") (pin "5") (pinfunction "CS_5") (pintype "output"))
    )
  )
)
